# CSI_FLAT.net
KiCad netlist of a schematic drawn in Altium Designer
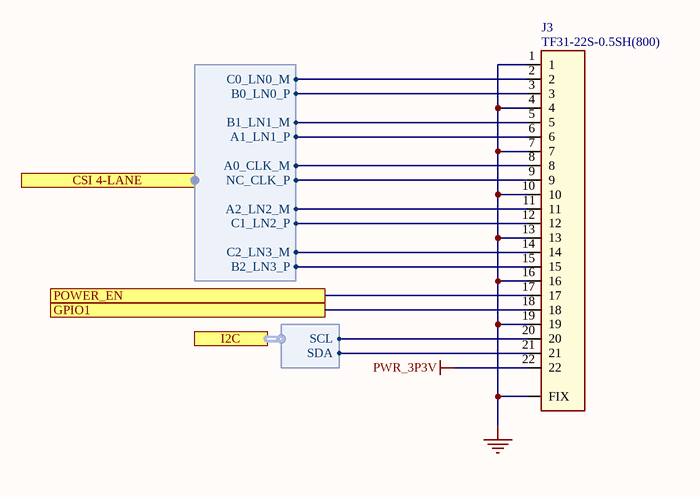
[diagram p0: CSI_FLAT.SchDoc]

(export (version "E")
  (design (tool "Eeschema 10.0.6"))
  (components
    (comp (ref "J3")
      (value "TF31-22S-0.5SH(800)")
      (footprint "TF31-22S-0.5SH(800)")
      (description "CONN FFC/FPC Connector, 22 Contact(s), 1 Row(s), BOTTOM CONTACT, Female, Right Angle, 0.5mm Pitch")
      (fields (field (name "MANUFACTURER") "Hirose"))
      (libsource (lib "Clean") (part "TF31-22S-0.5SH(800)"))
    )
  )
  (nets
    (net (code "3") (name "/A0_CLK_M") (class "Default")
      (node (ref "J3") (pin "8") (pinfunction "8_8") (pintype "passive"))
    )
    (net (code "4") (name "/A1_LN1_P") (class "Default")
      (node (ref "J3") (pin "6") (pinfunction "6_6") (pintype "passive"))
    )
    (net (code "5") (name "/A2_LN2_M") (class "Default")
      (node (ref "J3") (pin "11") (pinfunction "11_11") (pintype "passive"))
    )
    (net (code "6") (name "/B0_LN0_P") (class "Default")
      (node (ref "J3") (pin "3") (pinfunction "3_3") (pintype "passive"))
    )
    (net (code "7") (name "/B1_LN1_M") (class "Default")
      (node (ref "J3") (pin "5") (pinfunction "5_5") (pintype "passive"))
    )
    (net (code "8") (name "/B2_LN3_P") (class "Default")
      (node (ref "J3") (pin "15") (pinfunction "15_15") (pintype "passive"))
    )
    (net (code "9") (name "/C0_LN0_M") (class "Default")
      (node (ref "J3") (pin "2") (pinfunction "2_2") (pintype "passive"))
    )
    (net (code "10") (name "/C1_LN2_P") (class "Default")
      (node (ref "J3") (pin "12") (pinfunction "12_12") (pintype "passive"))
    )
    (net (code "11") (name "/C2_LN3_M") (class "Default")
      (node (ref "J3") (pin "14") (pinfunction "14_14") (pintype "passive"))
    )
    (net (code "12") (name "/GPIO1") (class "Default")
      (node (ref "J3") (pin "18") (pinfunction "18_18") (pintype "passive"))
    )
    (net (code "13") (name "/NC_CLK_P") (class "Default")
      (node (ref "J3") (pin "9") (pinfunction "9_9") (pintype "passive"))
    )
    (net (code "14") (name "/POWER_EN") (class "Default")
      (node (ref "J3") (pin "17") (pinfunction "17_17") (pintype "passive"))
    )
    (net (code "15") (name "/SCL") (class "Default")
      (node (ref "J3") (pin "20") (pinfunction "20_20") (pintype "passive"))
    )
    (net (code "16") (name "/SDA") (class "Default")
      (node (ref "J3") (pin "21") (pinfunction "21_21") (pintype "passive"))
    )
    (net (code "19") (name "GND") (class "Default")
      (node (ref "J3") (pin "1") (pinfunction "1_1") (pintype "passive"))
      (node (ref "J3") (pin "10") (pinfunction "10_10") (pintype "passive"))
      (node (ref "J3") (pin "13") (pinfunction "13_13") (pintype "passive"))
      (node (ref "J3") (pin "16") (pinfunction "16_16") (pintype "passive"))
      (node (ref "J3") (pin "19") (pinfunction "19_19") (pintype "passive"))
      (node (ref "J3") (pin "4") (pinfunction "4_4") (pintype "passive"))
      (node (ref "J3") (pin "7") (pinfunction "7_7") (pintype "passive"))
      (node (ref "J3") (pin "FIX") (pinfunction "FIX_FIX") (pintype "passive"))
    )
    (net (code "20") (name "PWR_3P3V") (class "Default")
      (node (ref "J3") (pin "22") (pinfunction "22_22") (pintype "passive"))
    )
  )
)
